# MA-USBA.net
KiCad netlist of a schematic drawn in Altium Designer
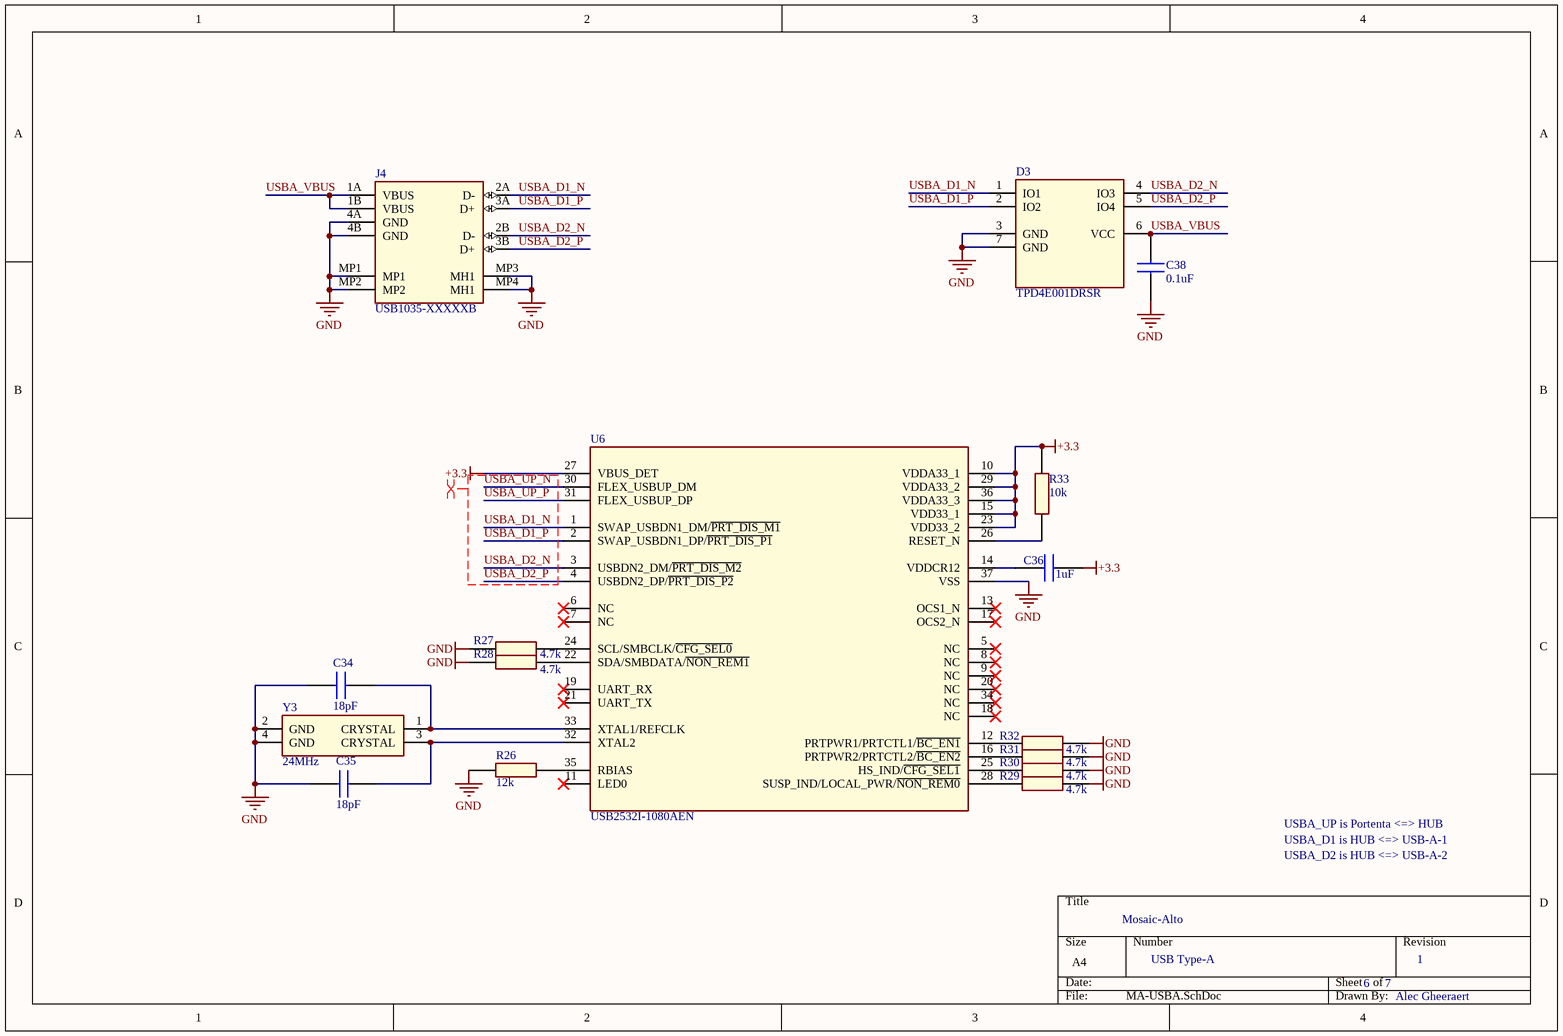
[diagram p0: MA-USBA.SchDoc]

(export (version "E")
  (design (tool "Eeschema 10.0.6"))
  (components
    (comp (ref "C34")
      (value "18pF")
      (footprint "CAPC1608X87N")
      (description "0603 18pF")
      (fields (field (name "TOLERANCE") "5%") (field (name "MANUFACTURER") "Walsin"))
      (libsource (lib "Ghrt") (part "0603N180J160CT"))
    )
    (comp (ref "C35")
      (value "18pF")
      (footprint "CAPC1608X87N")
      (description "0603 18pF")
      (fields (field (name "TOLERANCE") "5%") (field (name "MANUFACTURER") "Walsin"))
      (libsource (lib "Ghrt") (part "0603N180J160CT"))
    )
    (comp (ref "C36")
      (value "1uF")
      (footprint "CAPC1608X100N")
      (description "0603 1µF")
      (fields (field (name "MANUFACTURER") "Walsin") (field (name "TOLERANCE") "10%"))
      (libsource (lib "Ghrt") (part "0603X105K6R3CT"))
    )
    (comp (ref "C38")
      (value "0.1uF")
      (footprint "CAPC1005X55N")
      (description "0402I 0.1µF")
      (fields (field (name "MANUFACTURER") "Walsin") (field (name "TOLERANCE") "10%"))
      (libsource (lib "Ghrt") (part "MG15B104K100CT"))
    )
    (comp (ref "D3")
      (value "TPD4E001DRSR")
      (footprint "SON95P300X300X80-7N-D")
      (description "4-Channel TVS Diodes")
      (libsource (lib "Ghrt") (part "TPD4E001DRSR"))
    )
    (comp (ref "J4")
      (value "USB1035-XXXXXB")
      (footprint "USB1035-XXXXXB")
      (description "USB-2.0 Type A Dual")
      (fields (field (name "MANUFACTURER") "Global Connector Technologies"))
      (libsource (lib "Ghrt") (part "USB1035-XXXXXB"))
    )
    (comp (ref "R26")
      (value "12k")
      (footprint "RESC1005X40N")
      (description "0402I 12k")
      (fields (field (name "TOLERANCE") "1%") (field (name "MANUFACTURER") "Walsin"))
      (libsource (lib "Ghrt") (part "WR04X1202FTL"))
    )
    (comp (ref "R27")
      (value "4.7k")
      (footprint "RESC1005X40N")
      (description "0402I 4.7k")
      (fields (field (name "MANUFACTURER") "Walsin") (field (name "TOLERANCE") "1%"))
      (libsource (lib "Ghrt") (part "WR04X4701FTL"))
    )
    (comp (ref "R28")
      (value "4.7k")
      (footprint "RESC1005X40N")
      (description "0402I 4.7k")
      (fields (field (name "MANUFACTURER") "Walsin") (field (name "TOLERANCE") "1%"))
      (libsource (lib "Ghrt") (part "WR04X4701FTL"))
    )
    (comp (ref "R29")
      (value "4.7k")
      (footprint "RESC1005X40N")
      (description "0402I 4.7k")
      (fields (field (name "MANUFACTURER") "Walsin") (field (name "TOLERANCE") "1%"))
      (libsource (lib "") (part "WR04X4701FTL_1"))
    )
    (comp (ref "R30")
      (value "4.7k")
      (footprint "RESC1005X40N")
      (description "0402I 4.7k")
      (fields (field (name "MANUFACTURER") "Walsin") (field (name "TOLERANCE") "1%"))
      (libsource (lib "") (part "WR04X4701FTL_1"))
    )
    (comp (ref "R31")
      (value "4.7k")
      (footprint "RESC1005X40N")
      (description "0402I 4.7k")
      (fields (field (name "MANUFACTURER") "Walsin") (field (name "TOLERANCE") "1%"))
      (libsource (lib "") (part "WR04X4701FTL_1"))
    )
    (comp (ref "R32")
      (value "4.7k")
      (footprint "RESC1005X40N")
      (description "0402I 4.7k")
      (fields (field (name "MANUFACTURER") "Walsin") (field (name "TOLERANCE") "1%"))
      (libsource (lib "") (part "WR04X4701FTL_1"))
    )
    (comp (ref "R33")
      (value "10k")
      (footprint "RESC1005X40N")
      (description "0402I 10k")
      (fields (field (name "MANUFACTURER") "Walsin") (field (name "TOLERANCE") "1%"))
      (libsource (lib "Ghrt") (part "WR04X1002FTL"))
    )
    (comp (ref "U6")
      (value "USB2532I-1080AEN")
      (footprint "QFN50P600X600X100-37N-D")
      (description "2-Port USB-2.0 Controller Hub")
      (fields (field (name "MANUFACTURER") "Microchip"))
      (libsource (lib "Ghrt") (part "USB2532I-1080AEN"))
    )
    (comp (ref "Y3")
      (value "24MHz")
      (footprint "LFXTAL071257Reel")
      (description "24MHz +/-100ppm Crystal")
      (fields (field (name "TOLERANCE") "10") (field (name "MANUFACTURER") "IQD"))
      (libsource (lib "Ghrt") (part "LFXTAL071257Reel"))
    )
  )
  (nets
    (net (code "1") (name "+3.3") (class "Default")
      (node (ref "C36") (pin "2") (pinfunction "2_2") (pintype "passive"))
      (node (ref "R33") (pin "2") (pinfunction "2_2") (pintype "passive"))
      (node (ref "U6") (pin "10") (pinfunction "VDDA33_1_10") (pintype "passive"))
      (node (ref "U6") (pin "15") (pinfunction "VDD33_1_15") (pintype "passive"))
      (node (ref "U6") (pin "23") (pinfunction "VDD33_2_23") (pintype "passive"))
      (node (ref "U6") (pin "27") (pinfunction "VBUS_DET_27") (pintype "passive"))
      (node (ref "U6") (pin "29") (pinfunction "VDDA33_2_29") (pintype "passive"))
      (node (ref "U6") (pin "36") (pinfunction "VDDA33_3_36") (pintype "passive"))
    )
    (net (code "2") (name "/USBA_D1_N") (class "Default")
      (node (ref "D3") (pin "1") (pinfunction "IO1_1") (pintype "passive"))
      (node (ref "J4") (pin "2A") (pinfunction "D-_2A") (pintype "bidirectional"))
      (node (ref "U6") (pin "1") (pinfunction "SWAP_USBDN1_DM/~{PRT_DIS_M1}_1") (pintype "passive"))
    )
    (net (code "3") (name "/USBA_D1_P") (class "Default")
      (node (ref "D3") (pin "2") (pinfunction "IO2_2") (pintype "passive"))
      (node (ref "J4") (pin "3A") (pinfunction "D+_3A") (pintype "bidirectional"))
      (node (ref "U6") (pin "2") (pinfunction "SWAP_USBDN1_DP/~{PRT_DIS_P1}_2") (pintype "passive"))
    )
    (net (code "4") (name "/USBA_D2_N") (class "Default")
      (node (ref "D3") (pin "4") (pinfunction "IO3_4") (pintype "passive"))
      (node (ref "J4") (pin "2B") (pinfunction "D-_2B") (pintype "bidirectional"))
      (node (ref "U6") (pin "3") (pinfunction "USBDN2_DM/~{PRT_DIS_M2}_3") (pintype "passive"))
    )
    (net (code "5") (name "/USBA_D2_P") (class "Default")
      (node (ref "D3") (pin "5") (pinfunction "IO4_5") (pintype "passive"))
      (node (ref "J4") (pin "3B") (pinfunction "D+_3B") (pintype "bidirectional"))
      (node (ref "U6") (pin "4") (pinfunction "USBDN2_DP/~{PRT_DIS_P2}_4") (pintype "passive"))
    )
    (net (code "6") (name "/USBA_UP_N") (class "Default")
      (node (ref "U6") (pin "30") (pinfunction "FLEX_USBUP_DM_30") (pintype "passive"))
    )
    (net (code "7") (name "/USBA_UP_P") (class "Default")
      (node (ref "U6") (pin "31") (pinfunction "FLEX_USBUP_DP_31") (pintype "passive"))
    )
    (net (code "8") (name "/USBA_VBUS") (class "Default")
      (node (ref "C38") (pin "1") (pinfunction "1_1") (pintype "passive"))
      (node (ref "D3") (pin "6") (pinfunction "VCC_6") (pintype "passive"))
      (node (ref "J4") (pin "1A") (pinfunction "VBUS_1A") (pintype "power_in"))
      (node (ref "J4") (pin "1B") (pinfunction "VBUS_1B") (pintype "power_in"))
    )
    (net (code "9") (name "GND") (class "Default")
      (node (ref "C34") (pin "2") (pinfunction "2_2") (pintype "passive"))
      (node (ref "C35") (pin "2") (pinfunction "2_2") (pintype "passive"))
      (node (ref "C38") (pin "2") (pinfunction "2_2") (pintype "passive"))
      (node (ref "D3") (pin "3") (pinfunction "GND_3") (pintype "passive"))
      (node (ref "D3") (pin "7") (pinfunction "GND_7") (pintype "passive"))
      (node (ref "J4") (pin "4A") (pinfunction "GND_4A") (pintype "power_in"))
      (node (ref "J4") (pin "4B") (pinfunction "GND_4B") (pintype "power_in"))
      (node (ref "J4") (pin "MP1") (pinfunction "MP1_MP1") (pintype "passive"))
      (node (ref "J4") (pin "MP2") (pinfunction "MP2_MP2") (pintype "passive"))
      (node (ref "J4") (pin "MP3") (pinfunction "MH1_MP3") (pintype "passive"))
      (node (ref "J4") (pin "MP4") (pinfunction "MH1_MP4") (pintype "passive"))
      (node (ref "R26") (pin "2") (pinfunction "2_2") (pintype "passive"))
      (node (ref "R27") (pin "2") (pinfunction "2_2") (pintype "passive"))
      (node (ref "R28") (pin "2") (pinfunction "2_2") (pintype "passive"))
      (node (ref "R29") (pin "2") (pinfunction "2_2") (pintype "passive"))
      (node (ref "R30") (pin "2") (pinfunction "2_2") (pintype "passive"))
      (node (ref "R31") (pin "2") (pinfunction "2_2") (pintype "passive"))
      (node (ref "R32") (pin "2") (pinfunction "2_2") (pintype "passive"))
      (node (ref "U6") (pin "37") (pinfunction "VSS_37") (pintype "passive"))
      (node (ref "Y3") (pin "2") (pinfunction "GND_2") (pintype "passive"))
      (node (ref "Y3") (pin "4") (pinfunction "GND_4") (pintype "passive"))
    )
    (net (code "10") (name "Net-(U6-HS_IND{slash}~{CFG_SEL1})") (class "Default")
      (node (ref "R30") (pin "1") (pinfunction "1_1") (pintype "passive"))
      (node (ref "U6") (pin "25") (pinfunction "HS_IND/~{CFG_SEL1}_25") (pintype "passive"))
    )
    (net (code "11") (name "Net-(U6-PRTPWR1{slash}PRTCTL1{slash}~{BC_EN1})") (class "Default")
      (node (ref "R32") (pin "1") (pinfunction "1_1") (pintype "passive"))
      (node (ref "U6") (pin "12") (pinfunction "PRTPWR1/PRTCTL1/~{BC_EN1}_12") (pintype "passive"))
    )
    (net (code "12") (name "Net-(U6-PRTPWR2{slash}PRTCTL2{slash}~{BC_EN2})") (class "Default")
      (node (ref "R31") (pin "1") (pinfunction "1_1") (pintype "passive"))
      (node (ref "U6") (pin "16") (pinfunction "PRTPWR2/PRTCTL2/~{BC_EN2}_16") (pintype "passive"))
    )
    (net (code "13") (name "Net-(U6-RBIAS)") (class "Default")
      (node (ref "R26") (pin "1") (pinfunction "1_1") (pintype "passive"))
      (node (ref "U6") (pin "35") (pinfunction "RBIAS_35") (pintype "passive"))
    )
    (net (code "14") (name "Net-(U6-RESET_N)") (class "Default")
      (node (ref "R33") (pin "1") (pinfunction "1_1") (pintype "passive"))
      (node (ref "U6") (pin "26") (pinfunction "RESET_N_26") (pintype "passive"))
    )
    (net (code "15") (name "Net-(U6-SCL{slash}SMBCLK{slash}~{CFG_SEL0})") (class "Default")
      (node (ref "R27") (pin "1") (pinfunction "1_1") (pintype "passive"))
      (node (ref "U6") (pin "24") (pinfunction "SCL/SMBCLK/~{CFG_SEL0}_24") (pintype "passive"))
    )
    (net (code "16") (name "Net-(U6-SDA{slash}SMBDATA{slash}~{NON_REM1})") (class "Default")
      (node (ref "R28") (pin "1") (pinfunction "1_1") (pintype "passive"))
      (node (ref "U6") (pin "22") (pinfunction "SDA/SMBDATA/~{NON_REM1}_22") (pintype "passive"))
    )
    (net (code "17") (name "Net-(U6-SUSP_IND{slash}LOCAL_PWR{slash}~{NON_REM0})") (class "Default")
      (node (ref "R29") (pin "1") (pinfunction "1_1") (pintype "passive"))
      (node (ref "U6") (pin "28") (pinfunction "SUSP_IND/LOCAL_PWR/~{NON_REM0}_28") (pintype "passive"))
    )
    (net (code "18") (name "Net-(U6-VDDCR12)") (class "Default")
      (node (ref "C36") (pin "1") (pinfunction "1_1") (pintype "passive"))
      (node (ref "U6") (pin "14") (pinfunction "VDDCR12_14") (pintype "passive"))
    )
    (net (code "19") (name "Net-(U6-XTAL1{slash}REFCLK)") (class "Default")
      (node (ref "C34") (pin "1") (pinfunction "1_1") (pintype "passive"))
      (node (ref "U6") (pin "33") (pinfunction "XTAL1/REFCLK_33") (pintype "passive"))
      (node (ref "Y3") (pin "1") (pinfunction "CRYSTAL_1") (pintype "passive"))
    )
    (net (code "20") (name "Net-(U6-XTAL2)") (class "Default")
      (node (ref "C35") (pin "1") (pinfunction "1_1") (pintype "passive"))
      (node (ref "U6") (pin "32") (pinfunction "XTAL2_32") (pintype "passive"))
      (node (ref "Y3") (pin "3") (pinfunction "CRYSTAL_3") (pintype "passive"))
    )
    (net (code "21") (name "unconnected-(U6-LED0-Pad11)") (class "Default")
      (node (ref "U6") (pin "11") (pinfunction "LED0_11") (pintype "passive+no_connect"))
    )
    (net (code "22") (name "unconnected-(U6-NC-Pad5)") (class "Default")
      (node (ref "U6") (pin "5") (pinfunction "NC_5") (pintype "passive+no_connect"))
    )
    (net (code "23") (name "unconnected-(U6-NC-Pad6)") (class "Default")
      (node (ref "U6") (pin "6") (pinfunction "NC_6") (pintype "passive+no_connect"))
    )
    (net (code "24") (name "unconnected-(U6-NC-Pad7)") (class "Default")
      (node (ref "U6") (pin "7") (pinfunction "NC_7") (pintype "passive+no_connect"))
    )
    (net (code "25") (name "unconnected-(U6-NC-Pad8)") (class "Default")
      (node (ref "U6") (pin "8") (pinfunction "NC_8") (pintype "passive+no_connect"))
    )
    (net (code "26") (name "unconnected-(U6-NC-Pad9)") (class "Default")
      (node (ref "U6") (pin "9") (pinfunction "NC_9") (pintype "passive+no_connect"))
    )
    (net (code "27") (name "unconnected-(U6-NC-Pad18)") (class "Default")
      (node (ref "U6") (pin "18") (pinfunction "NC_18") (pintype "passive+no_connect"))
    )
    (net (code "28") (name "unconnected-(U6-NC-Pad20)") (class "Default")
      (node (ref "U6") (pin "20") (pinfunction "NC_20") (pintype "passive+no_connect"))
    )
    (net (code "29") (name "unconnected-(U6-NC-Pad34)") (class "Default")
      (node (ref "U6") (pin "34") (pinfunction "NC_34") (pintype "passive+no_connect"))
    )
    (net (code "30") (name "unconnected-(U6-OCS1_N-Pad13)") (class "Default")
      (node (ref "U6") (pin "13") (pinfunction "OCS1_N_13") (pintype "passive+no_connect"))
    )
    (net (code "31") (name "unconnected-(U6-OCS2_N-Pad17)") (class "Default")
      (node (ref "U6") (pin "17") (pinfunction "OCS2_N_17") (pintype "passive+no_connect"))
    )
    (net (code "32") (name "unconnected-(U6-UART_RX-Pad19)") (class "Default")
      (node (ref "U6") (pin "19") (pinfunction "UART_RX_19") (pintype "passive+no_connect"))
    )
    (net (code "33") (name "unconnected-(U6-UART_TX-Pad21)") (class "Default")
      (node (ref "U6") (pin "21") (pinfunction "UART_TX_21") (pintype "passive+no_connect"))
    )
  )
)
